# Pyro_Channel.net
KiCad netlist of a schematic drawn in Altium Designer
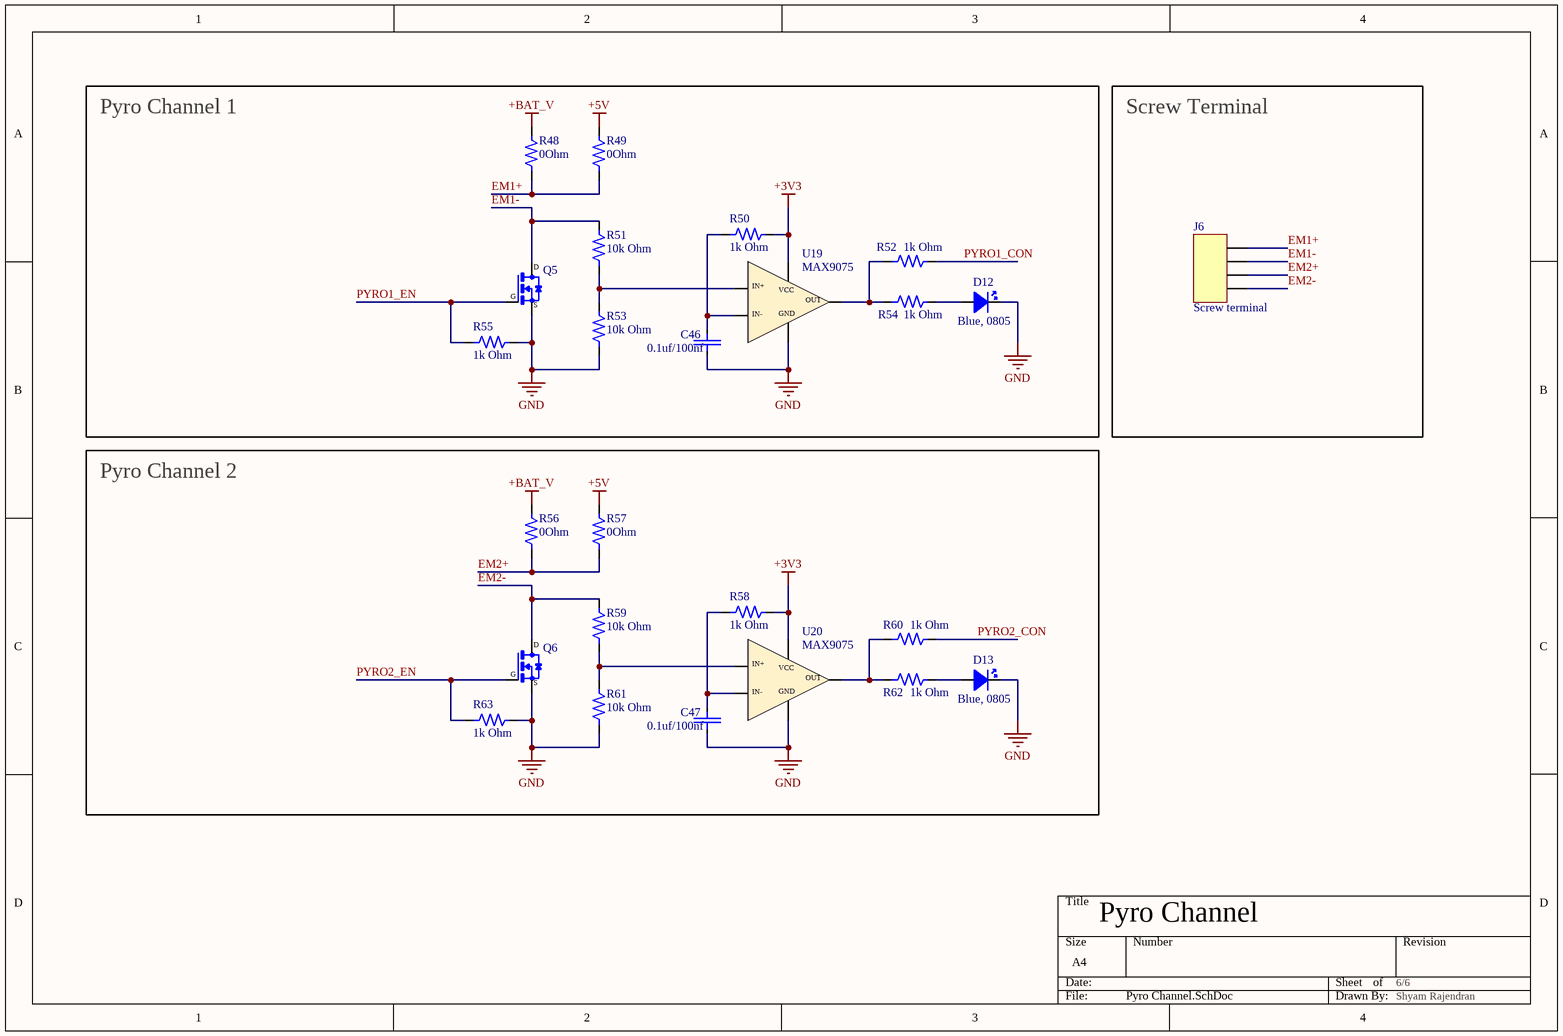
[diagram p0: Pyro Channel.SchDoc]

(export (version "E")
  (design (tool "Eeschema 10.0.6"))
  (components
    (comp (ref "C46")
      (value "0.1uf/100nf")
      (footprint "0.1uF Capacitor")
      (description "0.1 uF, Multilayer Ceramic Capacitor, 50 V, ï¿½ 10%, X7R, 0805 [2012 Metric]")
      (fields
        (field (name "MANUFACTURER") "Yageo")
        (field (name "MANUFACTURER PART NUMBER") "CC0805KRX7R9BB104")
      )
      (libsource (lib "Sirius") (part "CC0805KRX7R9BB104"))
    )
    (comp (ref "C47")
      (value "0.1uf/100nf")
      (footprint "0.1uF Capacitor")
      (description "0.1 uF, Multilayer Ceramic Capacitor, 50 V, ï¿½ 10%, X7R, 0805 [2012 Metric]")
      (fields
        (field (name "MANUFACTURER") "Yageo")
        (field (name "MANUFACTURER PART NUMBER") "CC0805KRX7R9BB104")
      )
      (libsource (lib "Sirius") (part "CC0805KRX7R9BB104"))
    )
    (comp (ref "D12")
      (value "Blue, 0805")
      (footprint "led blue")
      (libsource (lib "Sirius") (part "LED Blue"))
    )
    (comp (ref "D13")
      (value "Blue, 0805")
      (footprint "led blue")
      (libsource (lib "Sirius") (part "LED Blue"))
    )
    (comp (ref "J6")
      (value "Screw terminal")
      (footprint "Screw terminal")
      (description "5.08 pitch")
      (libsource (lib "Sirius") (part "screw terminal"))
    )
    (comp (ref "Q5")
      (value "WNM2021")
      (footprint "P Mosfet SL2P10A")
      (description "WNM2021-Slkor-20V 2.3A 86mΩ@2.5V,1A 200mW 1.2V 1 N-channel SOT-323 MOSFETs ROHS")
      (fields (field (name "MF") "Vishay Siliconix") (field (name "MP") "SI2323DS-T1-E3"))
      (libsource (lib "Sirius") (part "N Mosfet"))
    )
    (comp (ref "Q6")
      (value "WNM2021")
      (footprint "P Mosfet SL2P10A")
      (description "WNM2021-Slkor-20V 2.3A 86mΩ@2.5V,1A 200mW 1.2V 1 N-channel SOT-323 MOSFETs ROHS")
      (fields (field (name "MF") "Vishay Siliconix") (field (name "MP") "SI2323DS-T1-E3"))
      (libsource (lib "Sirius") (part "N Mosfet"))
    )
    (comp (ref "R48")
      (value "0Ohm")
      (footprint "1k 0805 Resistor")
      (description "0 Ohm Resistor, Jumper, 0805 [2012 Metric], Thick Film, 125 mW, Surface Mount")
      (fields
        (field (name "MANUFACTURER") "Vishay")
        (field (name "MANUFACTURER PART NUMBER") "CRCW08050000Z0EA")
      )
      (libsource (lib "Sirius") (part "CRCW08050000Z0EA"))
    )
    (comp (ref "R49")
      (value "0Ohm")
      (footprint "1k 0805 Resistor")
      (description "0 Ohm Resistor, Jumper, 0805 [2012 Metric], Thick Film, 125 mW, Surface Mount")
      (fields
        (field (name "MANUFACTURER") "Vishay")
        (field (name "MANUFACTURER PART NUMBER") "CRCW08050000Z0EA")
      )
      (libsource (lib "Sirius") (part "CRCW08050000Z0EA"))
    )
    (comp (ref "R50")
      (value "1k Ohm")
      (footprint "1k 0805 Resistor")
      (description "1k Ohm, 0805, SMD Chip Resistor , ï¿½ 1%, 125 mW,[2012 Metric], Thick Film, General Purpose")
      (fields
        (field (name "MANUFACTURER") "Yageo")
        (field (name "MANUFACTURER PART NUMBER") "RC0805FR-071KL")
      )
      (libsource (lib "Sirius") (part "RC0805FR-071KL"))
    )
    (comp (ref "R51")
      (value "10k Ohm")
      (footprint "RESC2013X60X35ML10T20")
      (description "10 kOhm, SMD Chip Resistor, ï¿½ 1%, 125 mW, 0805 [2012 Metric], Thick Film, General Purpose")
      (fields
        (field (name "MANUFACTURER") "Yageo")
        (field (name "MANUFACTURER PART NUMBER") "RC0805FR-0710KL")
      )
      (libsource (lib "Sirius") (part "RC0805FR-0710KL"))
    )
    (comp (ref "R52")
      (value "1k Ohm")
      (footprint "1k 0805 Resistor")
      (description "1k Ohm, 0805, SMD Chip Resistor , ï¿½ 1%, 125 mW,[2012 Metric], Thick Film, General Purpose")
      (fields
        (field (name "MANUFACTURER") "Yageo")
        (field (name "MANUFACTURER PART NUMBER") "RC0805FR-071KL")
      )
      (libsource (lib "Sirius") (part "RC0805FR-071KL"))
    )
    (comp (ref "R53")
      (value "10k Ohm")
      (footprint "RESC2013X60X35ML10T20")
      (description "10 kOhm, SMD Chip Resistor, ï¿½ 1%, 125 mW, 0805 [2012 Metric], Thick Film, General Purpose")
      (fields
        (field (name "MANUFACTURER") "Yageo")
        (field (name "MANUFACTURER PART NUMBER") "RC0805FR-0710KL")
      )
      (libsource (lib "Sirius") (part "RC0805FR-0710KL"))
    )
    (comp (ref "R54")
      (value "1k Ohm")
      (footprint "1k 0805 Resistor")
      (description "1k Ohm, 0805, SMD Chip Resistor , ï¿½ 1%, 125 mW,[2012 Metric], Thick Film, General Purpose")
      (fields
        (field (name "MANUFACTURER") "Yageo")
        (field (name "MANUFACTURER PART NUMBER") "RC0805FR-071KL")
      )
      (libsource (lib "Sirius") (part "RC0805FR-071KL"))
    )
    (comp (ref "R55")
      (value "1k Ohm")
      (footprint "1k 0805 Resistor")
      (description "1k Ohm, 0805, SMD Chip Resistor , ï¿½ 1%, 125 mW,[2012 Metric], Thick Film, General Purpose")
      (fields
        (field (name "MANUFACTURER") "Yageo")
        (field (name "MANUFACTURER PART NUMBER") "RC0805FR-071KL")
      )
      (libsource (lib "Sirius") (part "RC0805FR-071KL"))
    )
    (comp (ref "R56")
      (value "0Ohm")
      (footprint "1k 0805 Resistor")
      (description "0 Ohm Resistor, Jumper, 0805 [2012 Metric], Thick Film, 125 mW, Surface Mount")
      (fields
        (field (name "MANUFACTURER") "Vishay")
        (field (name "MANUFACTURER PART NUMBER") "CRCW08050000Z0EA")
      )
      (libsource (lib "Sirius") (part "CRCW08050000Z0EA"))
    )
    (comp (ref "R57")
      (value "0Ohm")
      (footprint "1k 0805 Resistor")
      (description "0 Ohm Resistor, Jumper, 0805 [2012 Metric], Thick Film, 125 mW, Surface Mount")
      (fields
        (field (name "MANUFACTURER") "Vishay")
        (field (name "MANUFACTURER PART NUMBER") "CRCW08050000Z0EA")
      )
      (libsource (lib "Sirius") (part "CRCW08050000Z0EA"))
    )
    (comp (ref "R58")
      (value "1k Ohm")
      (footprint "1k 0805 Resistor")
      (description "1k Ohm, 0805, SMD Chip Resistor , ï¿½ 1%, 125 mW,[2012 Metric], Thick Film, General Purpose")
      (fields
        (field (name "MANUFACTURER") "Yageo")
        (field (name "MANUFACTURER PART NUMBER") "RC0805FR-071KL")
      )
      (libsource (lib "Sirius") (part "RC0805FR-071KL"))
    )
    (comp (ref "R59")
      (value "10k Ohm")
      (footprint "RESC2013X60X35ML10T20")
      (description "10 kOhm, SMD Chip Resistor, ï¿½ 1%, 125 mW, 0805 [2012 Metric], Thick Film, General Purpose")
      (fields
        (field (name "MANUFACTURER") "Yageo")
        (field (name "MANUFACTURER PART NUMBER") "RC0805FR-0710KL")
      )
      (libsource (lib "Sirius") (part "RC0805FR-0710KL"))
    )
    (comp (ref "R60")
      (value "1k Ohm")
      (footprint "1k 0805 Resistor")
      (description "1k Ohm, 0805, SMD Chip Resistor , ï¿½ 1%, 125 mW,[2012 Metric], Thick Film, General Purpose")
      (fields
        (field (name "MANUFACTURER") "Yageo")
        (field (name "MANUFACTURER PART NUMBER") "RC0805FR-071KL")
      )
      (libsource (lib "Sirius") (part "RC0805FR-071KL"))
    )
    (comp (ref "R61")
      (value "10k Ohm")
      (footprint "RESC2013X60X35ML10T20")
      (description "10 kOhm, SMD Chip Resistor, ï¿½ 1%, 125 mW, 0805 [2012 Metric], Thick Film, General Purpose")
      (fields
        (field (name "MANUFACTURER") "Yageo")
        (field (name "MANUFACTURER PART NUMBER") "RC0805FR-0710KL")
      )
      (libsource (lib "Sirius") (part "RC0805FR-0710KL"))
    )
    (comp (ref "R62")
      (value "1k Ohm")
      (footprint "1k 0805 Resistor")
      (description "1k Ohm, 0805, SMD Chip Resistor , ï¿½ 1%, 125 mW,[2012 Metric], Thick Film, General Purpose")
      (fields
        (field (name "MANUFACTURER") "Yageo")
        (field (name "MANUFACTURER PART NUMBER") "RC0805FR-071KL")
      )
      (libsource (lib "Sirius") (part "RC0805FR-071KL"))
    )
    (comp (ref "R63")
      (value "1k Ohm")
      (footprint "1k 0805 Resistor")
      (description "1k Ohm, 0805, SMD Chip Resistor , ï¿½ 1%, 125 mW,[2012 Metric], Thick Film, General Purpose")
      (fields
        (field (name "MANUFACTURER") "Yageo")
        (field (name "MANUFACTURER PART NUMBER") "RC0805FR-071KL")
      )
      (libsource (lib "Sirius") (part "RC0805FR-071KL"))
    )
    (comp (ref "U19")
      (value "MAX9075")
      (footprint "Comparator MAX9075")
      (description "Comparator MAX9075 SOT23-5")
      (libsource (lib "Sirius") (part "Comparator MAX9075"))
    )
    (comp (ref "U20")
      (value "MAX9075")
      (footprint "Comparator MAX9075")
      (description "Comparator MAX9075 SOT23-5")
      (libsource (lib "Sirius") (part "Comparator MAX9075"))
    )
  )
  (nets
    (net (code "1") (name "+3V3") (class "Default")
      (node (ref "R50") (pin "2") (pinfunction "2_2") (pintype "passive"))
      (node (ref "R58") (pin "2") (pinfunction "2_2") (pintype "passive"))
      (node (ref "U19") (pin "VCC") (pinfunction "24_VCC") (pintype "passive"))
      (node (ref "U20") (pin "VCC") (pinfunction "24_VCC") (pintype "passive"))
    )
    (net (code "2") (name "+5V") (class "Default")
      (node (ref "R49") (pin "2") (pinfunction "2_2") (pintype "passive"))
      (node (ref "R57") (pin "2") (pinfunction "2_2") (pintype "passive"))
    )
    (net (code "3") (name "+BAT_V") (class "Default")
      (node (ref "R48") (pin "2") (pinfunction "2_2") (pintype "passive"))
      (node (ref "R56") (pin "2") (pinfunction "2_2") (pintype "passive"))
    )
    (net (code "4") (name "/EM1+") (class "Default")
      (node (ref "J6") (pin "1") (pinfunction "1_1") (pintype "passive"))
      (node (ref "R48") (pin "1") (pinfunction "1_1") (pintype "passive"))
      (node (ref "R49") (pin "1") (pinfunction "1_1") (pintype "passive"))
    )
    (net (code "5") (name "/EM1-") (class "Default")
      (node (ref "J6") (pin "2") (pinfunction "2_2") (pintype "passive"))
      (node (ref "Q5") (pin "D") (pinfunction "D_D") (pintype "passive"))
      (node (ref "R51") (pin "2") (pinfunction "2_2") (pintype "passive"))
    )
    (net (code "6") (name "/EM2+") (class "Default")
      (node (ref "J6") (pin "3") (pinfunction "3_3") (pintype "passive"))
      (node (ref "R56") (pin "1") (pinfunction "1_1") (pintype "passive"))
      (node (ref "R57") (pin "1") (pinfunction "1_1") (pintype "passive"))
    )
    (net (code "7") (name "/EM2-") (class "Default")
      (node (ref "J6") (pin "4") (pinfunction "4_4") (pintype "passive"))
      (node (ref "Q6") (pin "D") (pinfunction "D_D") (pintype "passive"))
      (node (ref "R59") (pin "2") (pinfunction "2_2") (pintype "passive"))
    )
    (net (code "8") (name "/PYRO1_CON") (class "Default")
      (node (ref "R52") (pin "2") (pinfunction "2_2") (pintype "passive"))
    )
    (net (code "9") (name "/PYRO1_EN") (class "Default")
      (node (ref "Q5") (pin "G") (pinfunction "G_G") (pintype "passive"))
      (node (ref "R55") (pin "1") (pinfunction "1_1") (pintype "passive"))
    )
    (net (code "10") (name "/PYRO2_CON") (class "Default")
      (node (ref "R60") (pin "2") (pinfunction "2_2") (pintype "passive"))
    )
    (net (code "11") (name "/PYRO2_EN") (class "Default")
      (node (ref "Q6") (pin "G") (pinfunction "G_G") (pintype "passive"))
      (node (ref "R63") (pin "1") (pinfunction "1_1") (pintype "passive"))
    )
    (net (code "12") (name "GND") (class "Default")
      (node (ref "C46") (pin "1") (pinfunction "1_1") (pintype "passive"))
      (node (ref "C47") (pin "1") (pinfunction "1_1") (pintype "passive"))
      (node (ref "D12") (pin "C") (pinfunction "2_C") (pintype "passive"))
      (node (ref "D13") (pin "C") (pinfunction "2_C") (pintype "passive"))
      (node (ref "Q5") (pin "S") (pinfunction "S_S") (pintype "passive"))
      (node (ref "Q6") (pin "S") (pinfunction "S_S") (pintype "passive"))
      (node (ref "R53") (pin "1") (pinfunction "1_1") (pintype "passive"))
      (node (ref "R55") (pin "2") (pinfunction "2_2") (pintype "passive"))
      (node (ref "R61") (pin "1") (pinfunction "1_1") (pintype "passive"))
      (node (ref "R63") (pin "2") (pinfunction "2_2") (pintype "passive"))
      (node (ref "U19") (pin "GND") (pinfunction "27_GND") (pintype "passive"))
      (node (ref "U20") (pin "GND") (pinfunction "27_GND") (pintype "passive"))
    )
    (net (code "13") (name "Net-(D12-1)") (class "Default")
      (node (ref "D12") (pin "A") (pinfunction "1_A") (pintype "passive"))
      (node (ref "R54") (pin "2") (pinfunction "2_2") (pintype "passive"))
    )
    (net (code "14") (name "Net-(D13-1)") (class "Default")
      (node (ref "D13") (pin "A") (pinfunction "1_A") (pintype "passive"))
      (node (ref "R62") (pin "2") (pinfunction "2_2") (pintype "passive"))
    )
    (net (code "15") (name "Net-(U19-25)") (class "Default")
      (node (ref "C46") (pin "2") (pinfunction "2_2") (pintype "passive"))
      (node (ref "R50") (pin "1") (pinfunction "1_1") (pintype "passive"))
      (node (ref "U19") (pin "IN-") (pinfunction "25_IN-") (pintype "passive"))
    )
    (net (code "16") (name "Net-(U19-26)") (class "Default")
      (node (ref "R52") (pin "1") (pinfunction "1_1") (pintype "passive"))
      (node (ref "R54") (pin "1") (pinfunction "1_1") (pintype "passive"))
      (node (ref "U19") (pin "OUT") (pinfunction "26_OUT") (pintype "passive"))
    )
    (net (code "17") (name "Net-(U19-28)") (class "Default")
      (node (ref "R51") (pin "1") (pinfunction "1_1") (pintype "passive"))
      (node (ref "R53") (pin "2") (pinfunction "2_2") (pintype "passive"))
      (node (ref "U19") (pin "IN+") (pinfunction "28_IN+") (pintype "passive"))
    )
    (net (code "18") (name "Net-(U20-25)") (class "Default")
      (node (ref "C47") (pin "2") (pinfunction "2_2") (pintype "passive"))
      (node (ref "R58") (pin "1") (pinfunction "1_1") (pintype "passive"))
      (node (ref "U20") (pin "IN-") (pinfunction "25_IN-") (pintype "passive"))
    )
    (net (code "19") (name "Net-(U20-26)") (class "Default")
      (node (ref "R60") (pin "1") (pinfunction "1_1") (pintype "passive"))
      (node (ref "R62") (pin "1") (pinfunction "1_1") (pintype "passive"))
      (node (ref "U20") (pin "OUT") (pinfunction "26_OUT") (pintype "passive"))
    )
    (net (code "20") (name "Net-(U20-28)") (class "Default")
      (node (ref "R59") (pin "1") (pinfunction "1_1") (pintype "passive"))
      (node (ref "R61") (pin "2") (pinfunction "2_2") (pintype "passive"))
      (node (ref "U20") (pin "IN+") (pinfunction "28_IN+") (pintype "passive"))
    )
  )
)
